# 08_-PowerSupply.net
KiCad netlist of a schematic drawn in Altium Designer
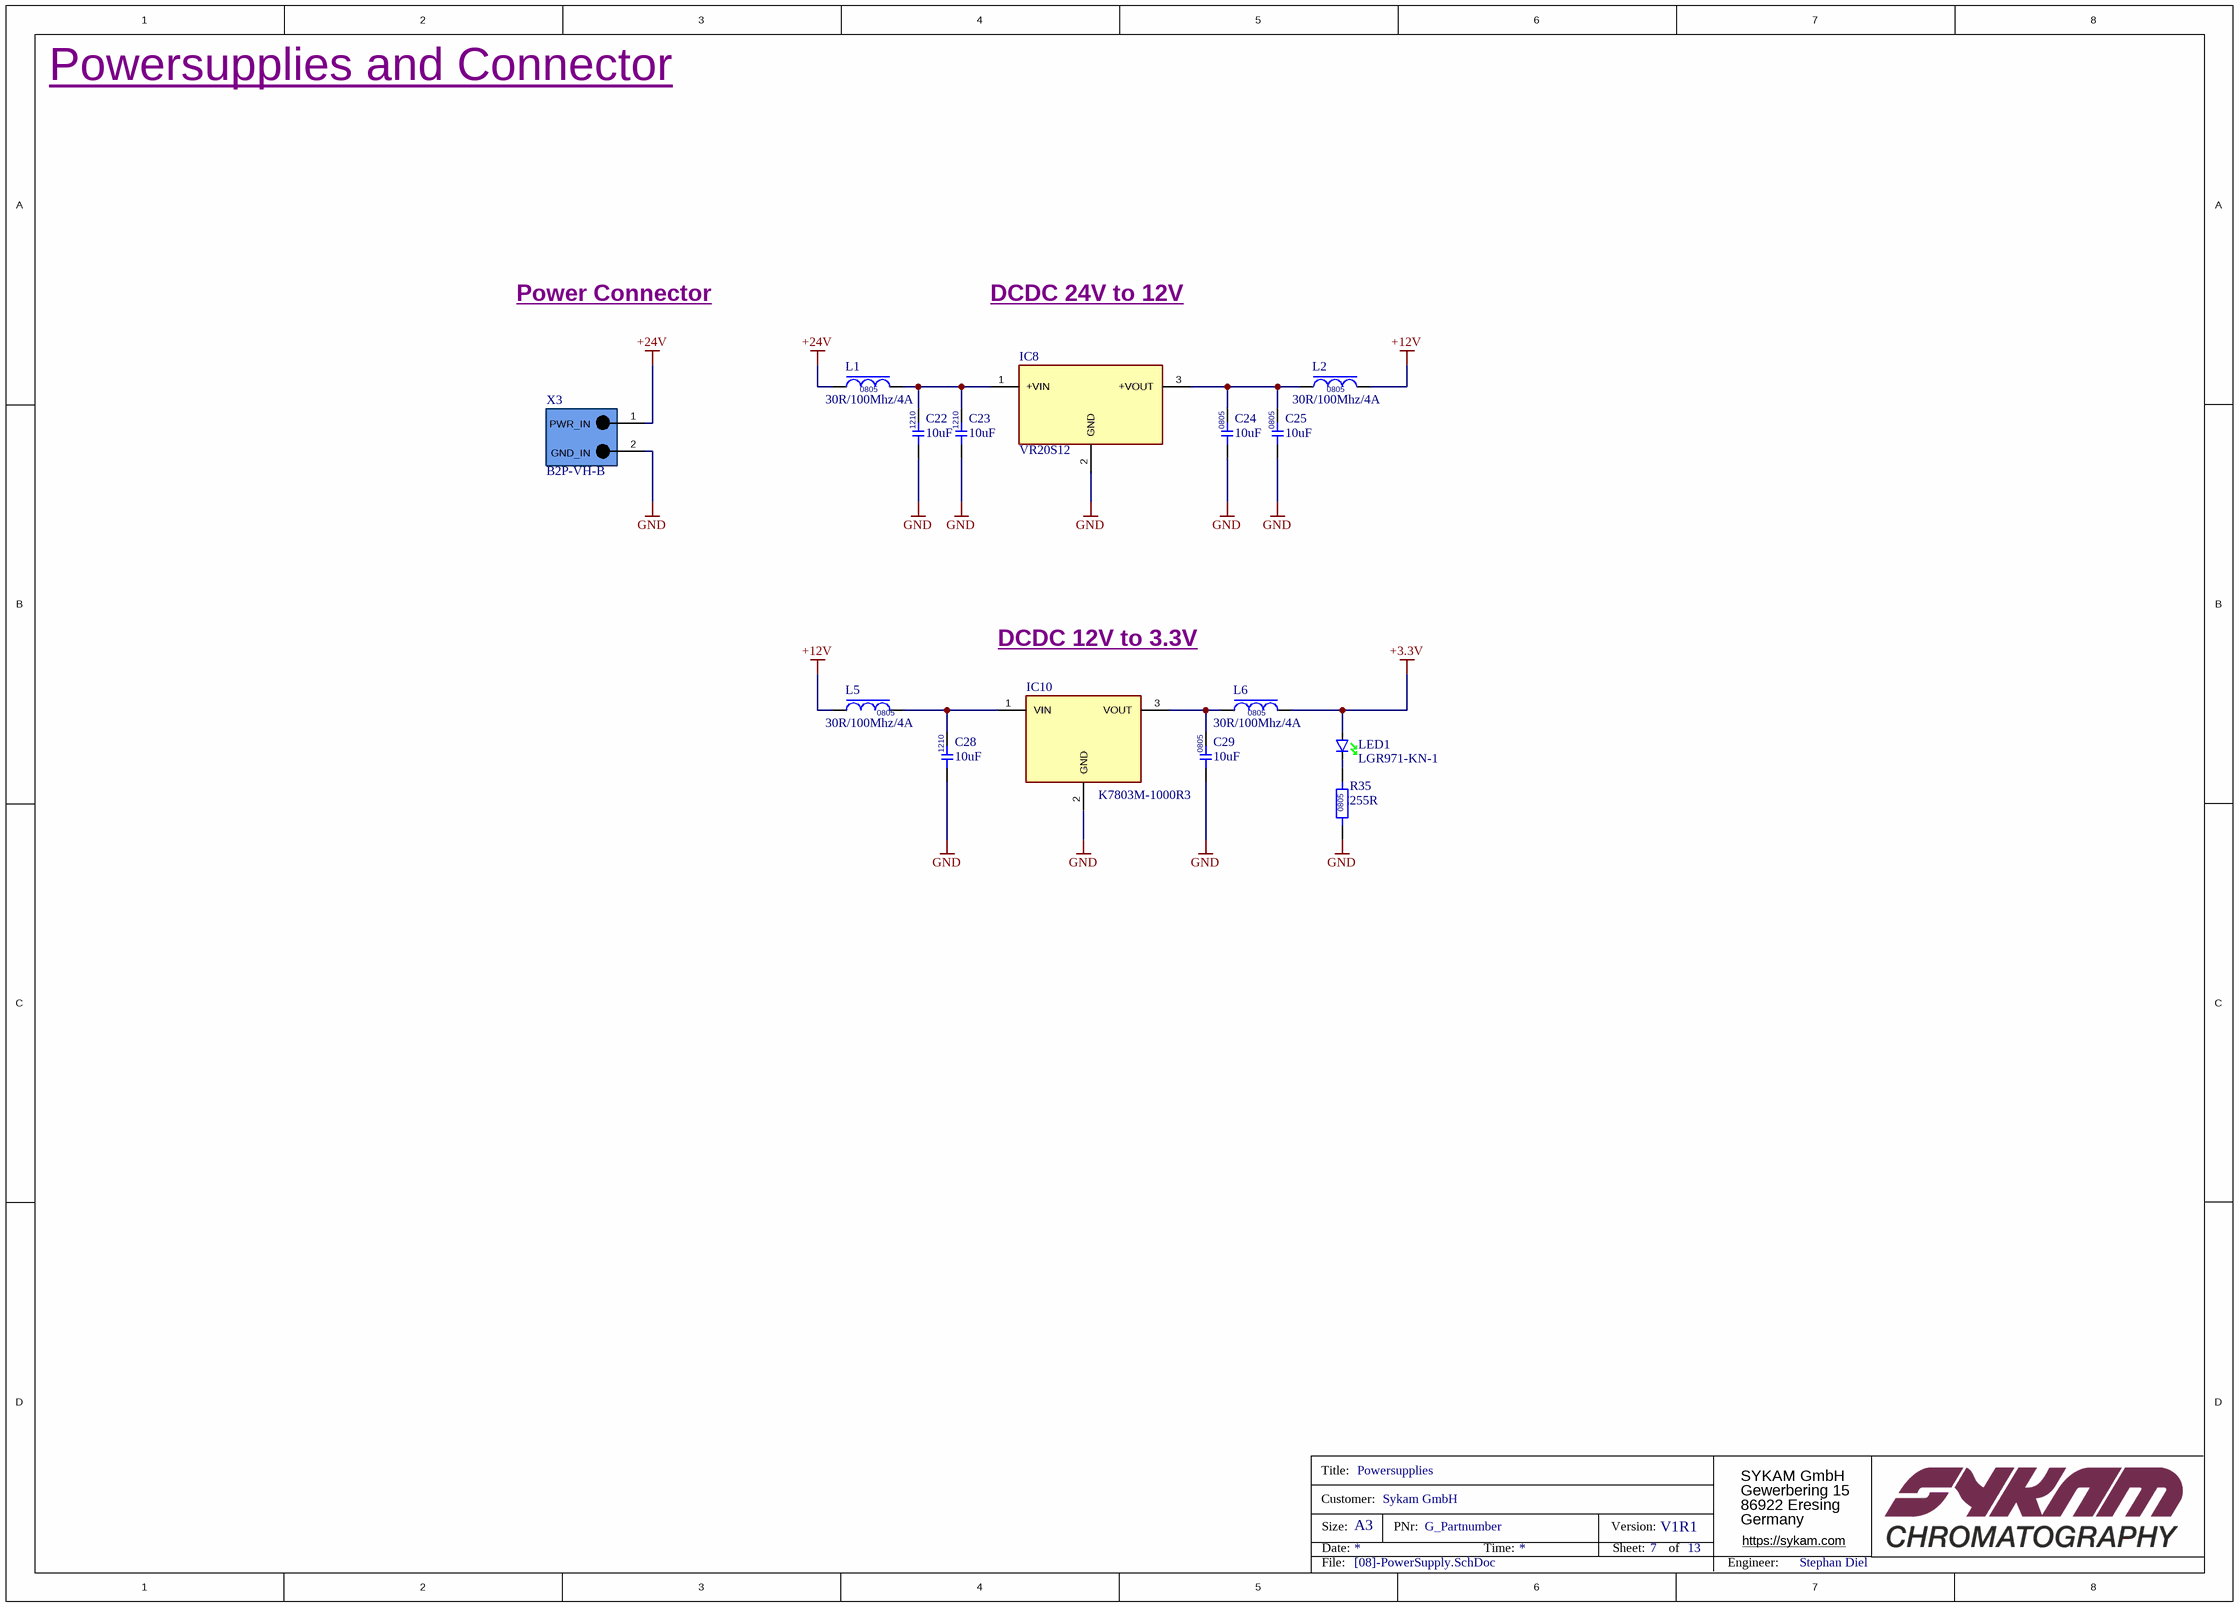
[diagram p0: [08]-PowerSupply.SchDoc]

(export (version "E")
  (design (tool "Eeschema 10.0.6"))
  (components
    (comp (ref "C22")
      (value "10uF")
      (footprint "C1210")
      (description "CAP CER 10UF 50V X7R 1210")
      (fields
        (field (name "MANUFACTURER") "KEMET")
        (field (name "MANUFACTURER PART NUMBER") "C1210C106K5RACTU")
      )
      (libsource (lib "ToradexMainBoard-V0I1") (part "C_10uF_C1210C106K5RACTU"))
    )
    (comp (ref "C23")
      (value "10uF")
      (footprint "C1210")
      (description "CAP CER 10UF 50V X7R 1210")
      (fields
        (field (name "MANUFACTURER") "KEMET")
        (field (name "MANUFACTURER PART NUMBER") "C1210C106K5RACTU")
      )
      (libsource (lib "ToradexMainBoard-V0I1") (part "C_10uF_C1210C106K5RACTU"))
    )
    (comp (ref "C24")
      (value "10uF")
      (footprint "C0805")
      (description "0805 10 uF 50 V ±20% Tolerance X5R Multilayer Ceramic Capacitor")
      (fields
        (field (name "MANUFACTURER") "Murata")
        (field (name "MANUFACTURER PART NUMBER") "GRM21BR6YA106ME43L")
      )
      (libsource (lib "ToradexMainBoard-V0I1") (part "C_10uF_GRM21BR6YA106ME43L"))
    )
    (comp (ref "C25")
      (value "10uF")
      (footprint "C0805")
      (description "0805 10 uF 50 V ±20% Tolerance X5R Multilayer Ceramic Capacitor")
      (fields
        (field (name "MANUFACTURER") "Murata")
        (field (name "MANUFACTURER PART NUMBER") "GRM21BR6YA106ME43L")
      )
      (libsource (lib "ToradexMainBoard-V0I1") (part "C_10uF_GRM21BR6YA106ME43L"))
    )
    (comp (ref "C28")
      (value "10uF")
      (footprint "C1210")
      (description "CAP CER 10UF 50V X7R 1210")
      (fields
        (field (name "MANUFACTURER") "KEMET")
        (field (name "MANUFACTURER PART NUMBER") "C1210C106K5RACTU")
      )
      (libsource (lib "ToradexMainBoard-V0I1") (part "C_10uF_C1210C106K5RACTU"))
    )
    (comp (ref "C29")
      (value "10uF")
      (footprint "C0805")
      (description "0805 10 uF 50 V ±20% Tolerance X5R Multilayer Ceramic Capacitor")
      (fields
        (field (name "MANUFACTURER") "Murata")
        (field (name "MANUFACTURER PART NUMBER") "GRM21BR6YA106ME43L")
      )
      (libsource (lib "ToradexMainBoard-V0I1") (part "C_10uF_GRM21BR6YA106ME43L"))
    )
    (comp (ref "IC8")
      (value "VR20S12")
      (footprint "IC_VR20S12_THT")
      (description "DC-DC Converter, Switching Regulater, 2A, SIP, VR Series")
      (fields (field (name "MANUFACTURER") "XP Power"))
      (libsource (lib "ToradexMainBoard-V0I1") (part "IC_VR20S12"))
    )
    (comp (ref "IC10")
      (value "K7803M-1000R3")
      (footprint "IC_K7803M-1000R3_THT")
      (description "Nichtisoliertes PoL-Modul DC/DC-Wandler 1 Ausgang 3,3V 1A 6V - 36V Eingang")
      (libsource (lib "ToradexMainBoard-V0I1") (part "IC_K7803M-1000R3"))
    )
    (comp (ref "L1")
      (value "30R/100Mhz/4A")
      (footprint "L0805")
      (description "Ferrite Beads Multi-Layer 30Ohm 100MHz 4A 14mOhm DCR 0805 T/R")
      (fields
        (field (name "MANUFACTURER PART NUMBER") "BLM21PG300SN1D")
        (field (name "TOLERANCE") "25%")
        (field (name "PCBCHECKED") "initials after Checked")
        (field (name "SCHCHECKED") "Initials after checked")
      )
      (libsource (lib "ToradexMainBoard-V0I1") (part "L_BLM21PG300SN1D"))
    )
    (comp (ref "L2")
      (value "30R/100Mhz/4A")
      (footprint "L0805")
      (description "Ferrite Beads Multi-Layer 30Ohm 100MHz 4A 14mOhm DCR 0805 T/R")
      (fields
        (field (name "MANUFACTURER PART NUMBER") "BLM21PG300SN1D")
        (field (name "TOLERANCE") "25%")
        (field (name "PCBCHECKED") "initials after Checked")
        (field (name "SCHCHECKED") "Initials after checked")
      )
      (libsource (lib "ToradexMainBoard-V0I1") (part "L_BLM21PG300SN1D"))
    )
    (comp (ref "L5")
      (value "30R/100Mhz/4A")
      (footprint "L0805")
      (description "Ferrite Beads Multi-Layer 30Ohm 100MHz 4A 14mOhm DCR 0805 T/R")
      (fields
        (field (name "MANUFACTURER PART NUMBER") "BLM21PG300SN1D")
        (field (name "TOLERANCE") "25%")
        (field (name "PCBCHECKED") "initials after Checked")
        (field (name "SCHCHECKED") "Initials after checked")
      )
      (libsource (lib "") (part "L_BLM21PG300SN1D_1"))
    )
    (comp (ref "L6")
      (value "30R/100Mhz/4A")
      (footprint "L0805")
      (description "Ferrite Beads Multi-Layer 30Ohm 100MHz 4A 14mOhm DCR 0805 T/R")
      (fields
        (field (name "MANUFACTURER PART NUMBER") "BLM21PG300SN1D")
        (field (name "TOLERANCE") "25%")
        (field (name "PCBCHECKED") "initials after Checked")
        (field (name "SCHCHECKED") "Initials after checked")
      )
      (libsource (lib "ToradexMainBoard-V0I1") (part "L_BLM21PG300SN1D"))
    )
    (comp (ref "LED1")
      (value "LGR971-KN-1")
      (footprint "LED0805")
      (description "LED Uni-Color Green 572nm 2-Pin SMD T/R")
      (fields (field (name "MANUFACTURER") "Osram Opto"))
      (libsource (lib "ToradexMainBoard-V0I1") (part "LED_LGR971-KN-1"))
    )
    (comp (ref "R35")
      (value "255R")
      (footprint "R0805")
      (description "Res Thick Film 0805 255 Ohm 1% 0.125W(1/8W) ±100ppm/C Epoxy SMD T/R")
      (fields
        (field (name "MANUFACTURER") "Yageo")
        (field (name "MANUFACTURER PART NUMBER") "RC0805FR-07255RL")
      )
      (libsource (lib "ToradexMainBoard-V0I1") (part "R_255R_RC0805FR-07255RL"))
    )
    (comp (ref "X3")
      (value "B2P-VH-B")
      (footprint "CON-B2P-VH-B-3.96MM_nn")
      (description "CONN HEADER TOP 2POS 3.96MM VH")
      (fields
        (field (name "MANUFACTURER PART NUMBER") "B2P-VH-B(LF)(SN)")
        (field (name "MANUFACTURER") "JST")
        (field (name "PCBCHECKED") "initials after Checked")
        (field (name "SCHCHECKED") "initials after Checked")
      )
      (libsource (lib "ToradexMainBoard-V0I1") (part "CON_2p_B2P-VH-B(LF)(SN)"))
    )
  )
  (nets
    (net (code "1") (name "+3.3V") (class "Default")
      (node (ref "L6") (pin "2") (pinfunction "2_2") (pintype "passive"))
      (node (ref "LED1") (pin "2A") (pinfunction "A_2A") (pintype "passive"))
    )
    (net (code "2") (name "+12V") (class "Default")
      (node (ref "L2") (pin "2") (pinfunction "2_2") (pintype "passive"))
      (node (ref "L5") (pin "2") (pinfunction "2_2") (pintype "passive"))
    )
    (net (code "3") (name "+24V") (class "Default")
      (node (ref "L1") (pin "1") (pinfunction "1_1") (pintype "passive"))
      (node (ref "X3") (pin "1") (pinfunction "GND_IN_1") (pintype "passive"))
    )
    (net (code "4") (name "GND") (class "Default")
      (node (ref "C22") (pin "1") (pinfunction "1_1") (pintype "passive"))
      (node (ref "C23") (pin "1") (pinfunction "1_1") (pintype "passive"))
      (node (ref "C24") (pin "1") (pinfunction "1_1") (pintype "passive"))
      (node (ref "C25") (pin "1") (pinfunction "1_1") (pintype "passive"))
      (node (ref "C28") (pin "1") (pinfunction "1_1") (pintype "passive"))
      (node (ref "C29") (pin "1") (pinfunction "1_1") (pintype "passive"))
      (node (ref "IC10") (pin "2") (pinfunction "GND_2") (pintype "power_in"))
      (node (ref "IC8") (pin "2") (pinfunction "GND_2") (pintype "power_in"))
      (node (ref "R35") (pin "1") (pinfunction "1_1") (pintype "passive"))
      (node (ref "X3") (pin "2") (pinfunction "PWR_IN_2") (pintype "passive"))
    )
    (net (code "5") (name "Net-(IC8-+VIN)") (class "Default")
      (node (ref "C22") (pin "2") (pinfunction "2_2") (pintype "passive"))
      (node (ref "C23") (pin "2") (pinfunction "2_2") (pintype "passive"))
      (node (ref "IC8") (pin "1") (pinfunction "+VIN_1") (pintype "power_in"))
      (node (ref "L1") (pin "2") (pinfunction "2_2") (pintype "passive"))
    )
    (net (code "6") (name "Net-(IC8-+VOUT)") (class "Default")
      (node (ref "C24") (pin "2") (pinfunction "2_2") (pintype "passive"))
      (node (ref "C25") (pin "2") (pinfunction "2_2") (pintype "passive"))
      (node (ref "IC8") (pin "3") (pinfunction "+VOUT_3") (pintype "power_in"))
      (node (ref "L2") (pin "1") (pinfunction "1_1") (pintype "passive"))
    )
    (net (code "7") (name "Net-(IC10-VIN)") (class "Default")
      (node (ref "C28") (pin "2") (pinfunction "2_2") (pintype "passive"))
      (node (ref "IC10") (pin "1") (pinfunction "VIN_1") (pintype "power_in"))
      (node (ref "L5") (pin "1") (pinfunction "1_1") (pintype "passive"))
    )
    (net (code "8") (name "Net-(IC10-VOUT)") (class "Default")
      (node (ref "C29") (pin "2") (pinfunction "2_2") (pintype "passive"))
      (node (ref "IC10") (pin "3") (pinfunction "VOUT_3") (pintype "power_in"))
      (node (ref "L6") (pin "1") (pinfunction "1_1") (pintype "passive"))
    )
    (net (code "9") (name "Net-(LED1-K)") (class "Default")
      (node (ref "LED1") (pin "1K") (pinfunction "K_1K") (pintype "passive"))
      (node (ref "R35") (pin "2") (pinfunction "2_2") (pintype "passive"))
    )
  )
)
